# LED_BUFFER.net
KiCad netlist of a schematic drawn in Altium Designer
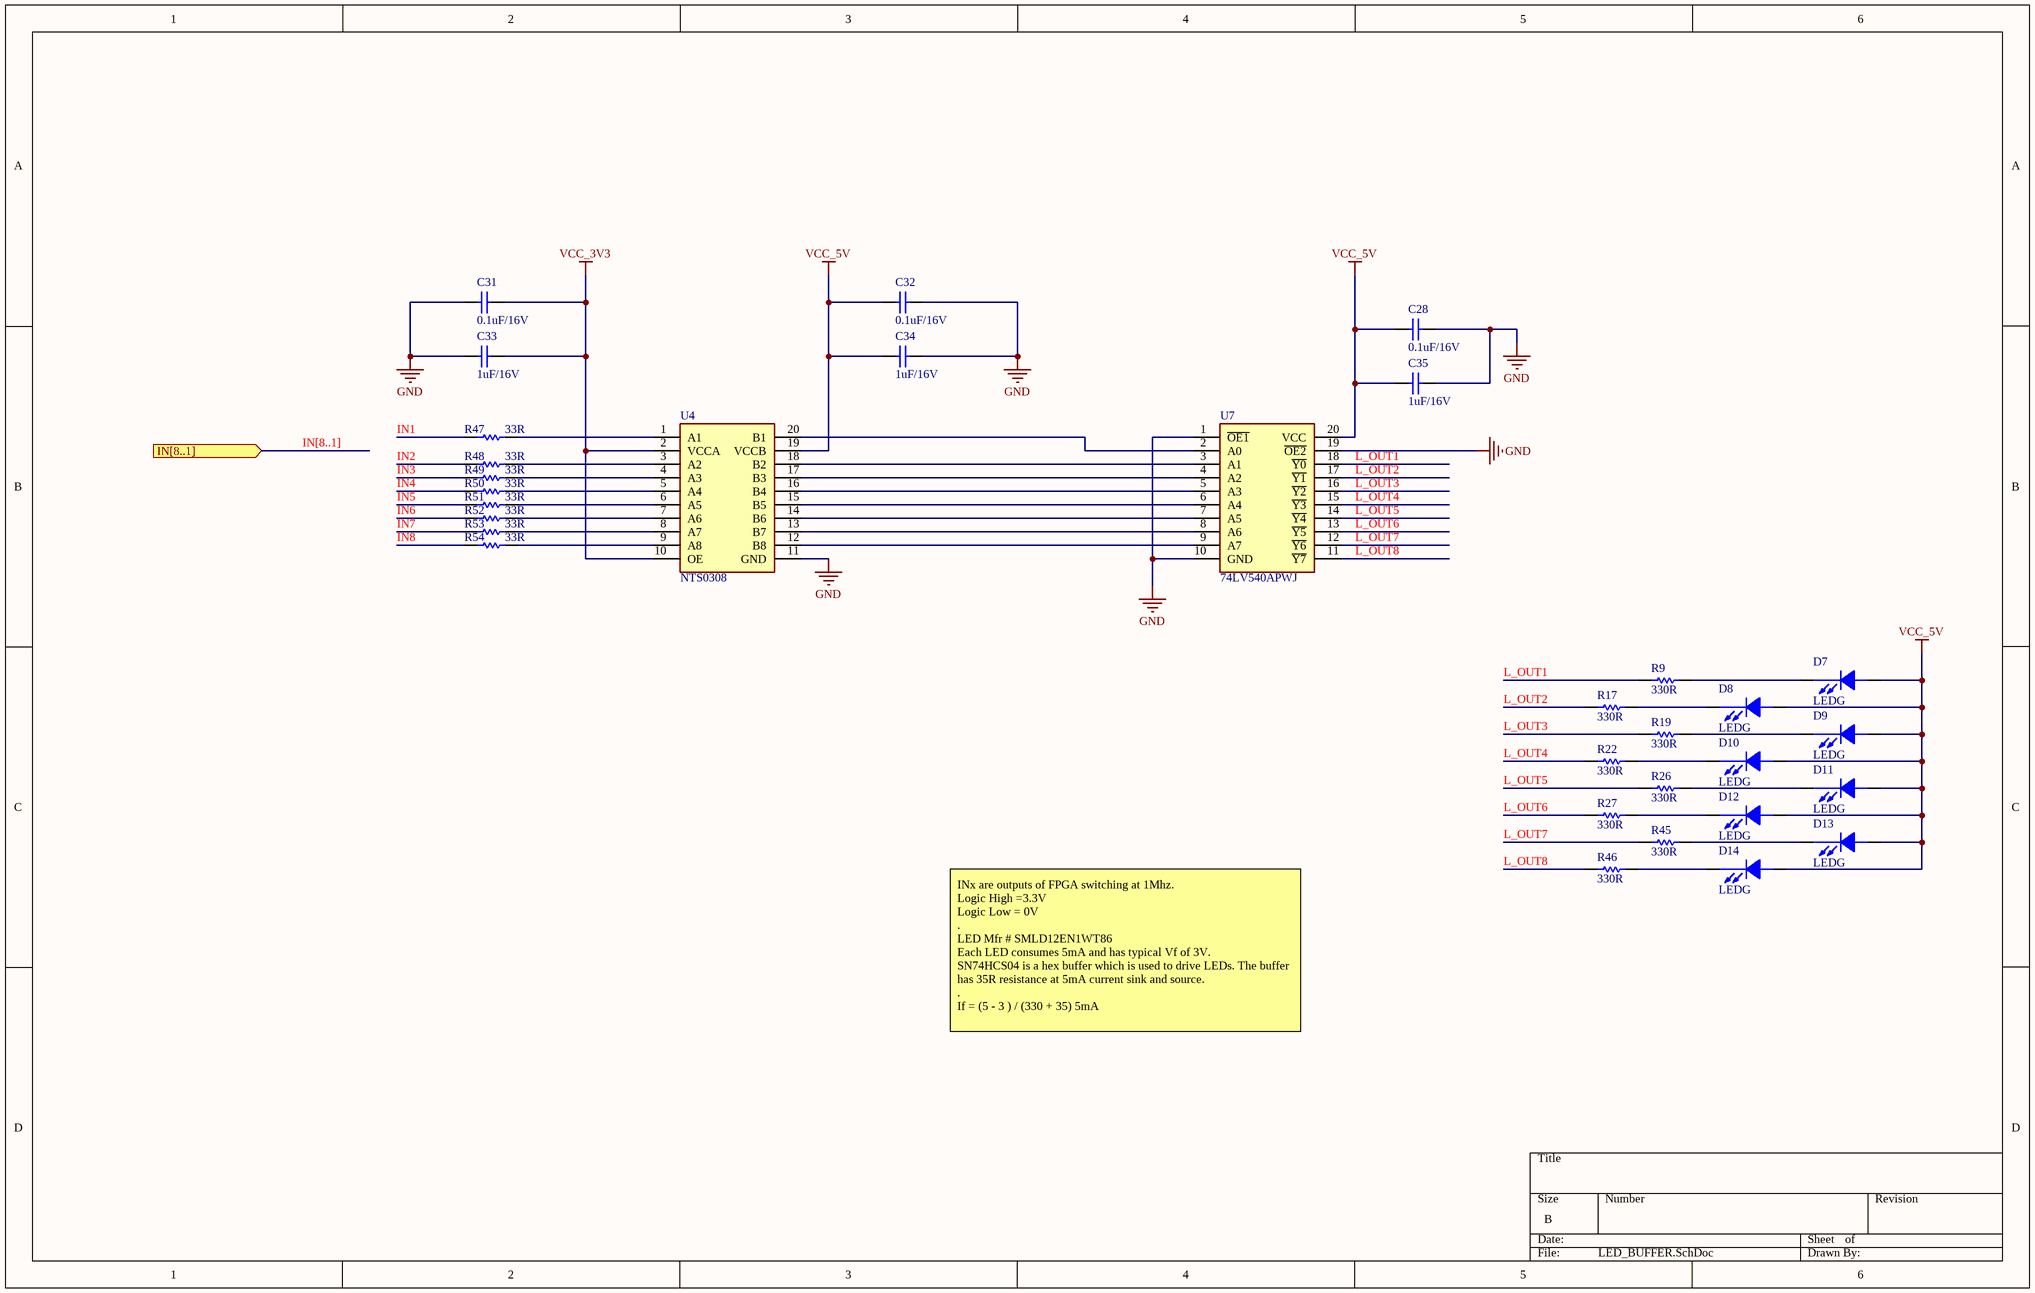
[diagram p0: LED_BUFFER.SchDoc]

(export (version "E")
  (design (tool "Eeschema 10.0.6"))
  (components
    (comp (ref "C28")
      (value "0.1uF/16V")
      (footprint "0603C")
      (description "Multilayer Ceramic Capacitors MLCC - SMD/SMT 0603 16VDC 0.1uF 10% X7R AEC-Q200")
      (fields (field (name "MFR") "Taiyo Yuden") (field (name "MFR PART NO") "EMK107B7104KAHT"))
      (libsource (lib "Miscellaneous Devices") (part "Cap"))
    )
    (comp (ref "C31")
      (value "0.1uF/16V")
      (footprint "0603C")
      (description "Multilayer Ceramic Capacitors MLCC - SMD/SMT 0603 16VDC 0.1uF 10% X7R AEC-Q200")
      (fields (field (name "MFR") "Taiyo Yuden") (field (name "MFR PART NO") "EMK107B7104KAHT"))
      (libsource (lib "Miscellaneous Devices") (part "Cap"))
    )
    (comp (ref "C32")
      (value "0.1uF/16V")
      (footprint "0603C")
      (description "Multilayer Ceramic Capacitors MLCC - SMD/SMT 0603 16VDC 0.1uF 10% X7R AEC-Q200")
      (fields (field (name "MFR") "Taiyo Yuden") (field (name "MFR PART NO") "EMK107B7104KAHT"))
      (libsource (lib "Miscellaneous Devices") (part "Cap"))
    )
    (comp (ref "C33")
      (value "1uF/16V")
      (footprint "0603C")
      (description "Multilayer Ceramic Capacitors MLCC - SMD/SMT 16volts 1uF X7R 10%")
      (fields (field (name "MFR") "KEMET") (field (name "MFR PART NO") "C0603C105K4RACTU"))
      (libsource (lib "Miscellaneous Devices") (part "Cap"))
    )
    (comp (ref "C34")
      (value "1uF/16V")
      (footprint "0603C")
      (description "Multilayer Ceramic Capacitors MLCC - SMD/SMT 16volts 1uF X7R 10%")
      (fields (field (name "MFR") "KEMET") (field (name "MFR PART NO") "C0603C105K4RACTU"))
      (libsource (lib "Miscellaneous Devices") (part "Cap"))
    )
    (comp (ref "C35")
      (value "1uF/16V")
      (footprint "0603C")
      (description "Multilayer Ceramic Capacitors MLCC - SMD/SMT 16volts 1uF X7R 10%")
      (fields (field (name "MFR") "KEMET") (field (name "MFR PART NO") "C0603C105K4RACTU"))
      (libsource (lib "Miscellaneous Devices") (part "Cap"))
    )
    (comp (ref "D7")
      (value "LEDG")
      (footprint "LED_0603")
      (description "Standard LEDs - SMD Grn 527nm; 140mcd 0603; 70mW")
      (fields (field (name "MFR") "ROHM Semiconductor") (field (name "MFR PART NO") "SMLD12EN1WT86"))
      (libsource (lib "de20") (part "LED"))
    )
    (comp (ref "D8")
      (value "LEDG")
      (footprint "LED_0603")
      (description "Standard LEDs - SMD Grn 527nm; 140mcd 0603; 70mW")
      (fields (field (name "MFR") "ROHM Semiconductor") (field (name "MFR PART NO") "SMLD12EN1WT86"))
      (libsource (lib "de20") (part "LED"))
    )
    (comp (ref "D9")
      (value "LEDG")
      (footprint "LED_0603")
      (description "Standard LEDs - SMD Grn 527nm; 140mcd 0603; 70mW")
      (fields (field (name "MFR") "ROHM Semiconductor") (field (name "MFR PART NO") "SMLD12EN1WT86"))
      (libsource (lib "de20") (part "LED"))
    )
    (comp (ref "D10")
      (value "LEDG")
      (footprint "LED_0603")
      (description "Standard LEDs - SMD Grn 527nm; 140mcd 0603; 70mW")
      (fields (field (name "MFR") "ROHM Semiconductor") (field (name "MFR PART NO") "SMLD12EN1WT86"))
      (libsource (lib "de20") (part "LED"))
    )
    (comp (ref "D11")
      (value "LEDG")
      (footprint "LED_0603")
      (description "Standard LEDs - SMD Grn 527nm; 140mcd 0603; 70mW")
      (fields (field (name "MFR") "ROHM Semiconductor") (field (name "MFR PART NO") "SMLD12EN1WT86"))
      (libsource (lib "de20") (part "LED"))
    )
    (comp (ref "D12")
      (value "LEDG")
      (footprint "LED_0603")
      (description "Standard LEDs - SMD Grn 527nm; 140mcd 0603; 70mW")
      (fields (field (name "MFR") "ROHM Semiconductor") (field (name "MFR PART NO") "SMLD12EN1WT86"))
      (libsource (lib "de20") (part "LED"))
    )
    (comp (ref "D13")
      (value "LEDG")
      (footprint "LED_0603")
      (description "Standard LEDs - SMD Grn 527nm; 140mcd 0603; 70mW")
      (fields (field (name "MFR") "ROHM Semiconductor") (field (name "MFR PART NO") "SMLD12EN1WT86"))
      (libsource (lib "de20") (part "LED"))
    )
    (comp (ref "D14")
      (value "LEDG")
      (footprint "LED_0603")
      (description "Standard LEDs - SMD Grn 527nm; 140mcd 0603; 70mW")
      (fields (field (name "MFR") "ROHM Semiconductor") (field (name "MFR PART NO") "SMLD12EN1WT86"))
      (libsource (lib "de20") (part "LED"))
    )
    (comp (ref "R9")
      (value "330R")
      (footprint "0603R")
      (description "Thick Film Resistors - SMD 1/10Watt 330ohms 1% Commercial Use")
      (fields (field (name "MFR") "Vishay / Dale") (field (name "MFR PART NO") "CRCW0603330RFKEAC"))
      (libsource (lib "Miscellaneous Devices") (part "Res1"))
    )
    (comp (ref "R17")
      (value "330R")
      (footprint "0603R")
      (description "Thick Film Resistors - SMD 1/10Watt 330ohms 1% Commercial Use")
      (fields (field (name "MFR") "Vishay / Dale") (field (name "MFR PART NO") "CRCW0603330RFKEAC"))
      (libsource (lib "Miscellaneous Devices") (part "Res1"))
    )
    (comp (ref "R19")
      (value "330R")
      (footprint "0603R")
      (description "Thick Film Resistors - SMD 1/10Watt 330ohms 1% Commercial Use")
      (fields (field (name "MFR") "Vishay / Dale") (field (name "MFR PART NO") "CRCW0603330RFKEAC"))
      (libsource (lib "Miscellaneous Devices") (part "Res1"))
    )
    (comp (ref "R22")
      (value "330R")
      (footprint "0603R")
      (description "Thick Film Resistors - SMD 1/10Watt 330ohms 1% Commercial Use")
      (fields (field (name "MFR") "Vishay / Dale") (field (name "MFR PART NO") "CRCW0603330RFKEAC"))
      (libsource (lib "Miscellaneous Devices") (part "Res1"))
    )
    (comp (ref "R26")
      (value "330R")
      (footprint "0603R")
      (description "Thick Film Resistors - SMD 1/10Watt 330ohms 1% Commercial Use")
      (fields (field (name "MFR") "Vishay / Dale") (field (name "MFR PART NO") "CRCW0603330RFKEAC"))
      (libsource (lib "Miscellaneous Devices") (part "Res1"))
    )
    (comp (ref "R27")
      (value "330R")
      (footprint "0603R")
      (description "Thick Film Resistors - SMD 1/10Watt 330ohms 1% Commercial Use")
      (fields (field (name "MFR") "Vishay / Dale") (field (name "MFR PART NO") "CRCW0603330RFKEAC"))
      (libsource (lib "Miscellaneous Devices") (part "Res1"))
    )
    (comp (ref "R45")
      (value "330R")
      (footprint "0603R")
      (description "Thick Film Resistors - SMD 1/10Watt 330ohms 1% Commercial Use")
      (fields (field (name "MFR") "Vishay / Dale") (field (name "MFR PART NO") "CRCW0603330RFKEAC"))
      (libsource (lib "Miscellaneous Devices") (part "Res1"))
    )
    (comp (ref "R46")
      (value "330R")
      (footprint "0603R")
      (description "Thick Film Resistors - SMD 1/10Watt 330ohms 1% Commercial Use")
      (fields (field (name "MFR") "Vishay / Dale") (field (name "MFR PART NO") "CRCW0603330RFKEAC"))
      (libsource (lib "Miscellaneous Devices") (part "Res1"))
    )
    (comp (ref "R47")
      (value "33R")
      (footprint "0603R")
      (description "Thick Film Resistors - SMD 1/10Watt 33ohms 1% Commercial Use")
      (fields (field (name "MFR") "Vishay / Dale") (field (name "MFR PART NO") "CRCW060333R0FKEAC"))
      (libsource (lib "Miscellaneous Devices") (part "Res1"))
    )
    (comp (ref "R48")
      (value "33R")
      (footprint "0603R")
      (description "Thick Film Resistors - SMD 1/10Watt 33ohms 1% Commercial Use")
      (fields (field (name "MFR") "Vishay / Dale") (field (name "MFR PART NO") "CRCW060333R0FKEAC"))
      (libsource (lib "Miscellaneous Devices") (part "Res1"))
    )
    (comp (ref "R49")
      (value "33R")
      (footprint "0603R")
      (description "Thick Film Resistors - SMD 1/10Watt 33ohms 1% Commercial Use")
      (fields (field (name "MFR") "Vishay / Dale") (field (name "MFR PART NO") "CRCW060333R0FKEAC"))
      (libsource (lib "Miscellaneous Devices") (part "Res1"))
    )
    (comp (ref "R50")
      (value "33R")
      (footprint "0603R")
      (description "Thick Film Resistors - SMD 1/10Watt 33ohms 1% Commercial Use")
      (fields (field (name "MFR") "Vishay / Dale") (field (name "MFR PART NO") "CRCW060333R0FKEAC"))
      (libsource (lib "Miscellaneous Devices") (part "Res1"))
    )
    (comp (ref "R51")
      (value "33R")
      (footprint "0603R")
      (description "Thick Film Resistors - SMD 1/10Watt 33ohms 1% Commercial Use")
      (fields (field (name "MFR") "Vishay / Dale") (field (name "MFR PART NO") "CRCW060333R0FKEAC"))
      (libsource (lib "Miscellaneous Devices") (part "Res1"))
    )
    (comp (ref "R52")
      (value "33R")
      (footprint "0603R")
      (description "Thick Film Resistors - SMD 1/10Watt 33ohms 1% Commercial Use")
      (fields (field (name "MFR") "Vishay / Dale") (field (name "MFR PART NO") "CRCW060333R0FKEAC"))
      (libsource (lib "Miscellaneous Devices") (part "Res1"))
    )
    (comp (ref "R53")
      (value "33R")
      (footprint "0603R")
      (description "Thick Film Resistors - SMD 1/10Watt 33ohms 1% Commercial Use")
      (fields (field (name "MFR") "Vishay / Dale") (field (name "MFR PART NO") "CRCW060333R0FKEAC"))
      (libsource (lib "Miscellaneous Devices") (part "Res1"))
    )
    (comp (ref "R54")
      (value "33R")
      (footprint "0603R")
      (description "Thick Film Resistors - SMD 1/10Watt 33ohms 1% Commercial Use")
      (fields (field (name "MFR") "Vishay / Dale") (field (name "MFR PART NO") "CRCW060333R0FKEAC"))
      (libsource (lib "Miscellaneous Devices") (part "Res1"))
    )
    (comp (ref "U4")
      (value "NTS0308")
      (footprint "NTS0308EPWJ")
      (fields
        (field (name "MFR") "NXP Semiconductors")
        (field (name "MFR PART NO") "NTS0308EPWJ")
        (field (name "STOCKIEST PART NO") "771-NTS0308EPWJ")
      )
      (libsource (lib "*") (part "TXS0108EPWR"))
    )
    (comp (ref "U7")
      (value "74LV540APWJ")
      (footprint "SamacSys:SOP65P640X110-20N")
      (description "Buffers & Line Drivers BUFFER LINE DRIVER")
      (fields (field (name "MFR") "Nexperia") (field (name "STOCKIEST PART NO") "771-74LV540APWJ"))
      (libsource (lib "*") (part "74LV540APWJ"))
    )
  )
  (nets
    (net (code "1") (name "/IN1") (class "Default")
      (node (ref "R47") (pin "2") (pinfunction "2_2") (pintype "passive"))
    )
    (net (code "2") (name "/IN2") (class "Default")
      (node (ref "R48") (pin "2") (pinfunction "2_2") (pintype "passive"))
    )
    (net (code "3") (name "/IN3") (class "Default")
      (node (ref "R49") (pin "2") (pinfunction "2_2") (pintype "passive"))
    )
    (net (code "4") (name "/IN4") (class "Default")
      (node (ref "R50") (pin "2") (pinfunction "2_2") (pintype "passive"))
    )
    (net (code "5") (name "/IN5") (class "Default")
      (node (ref "R51") (pin "2") (pinfunction "2_2") (pintype "passive"))
    )
    (net (code "6") (name "/IN6") (class "Default")
      (node (ref "R52") (pin "2") (pinfunction "2_2") (pintype "passive"))
    )
    (net (code "7") (name "/IN7") (class "Default")
      (node (ref "R53") (pin "2") (pinfunction "2_2") (pintype "passive"))
    )
    (net (code "8") (name "/IN8") (class "Default")
      (node (ref "R54") (pin "2") (pinfunction "2_2") (pintype "passive"))
    )
    (net (code "10") (name "/L_OUT1") (class "Default")
      (node (ref "R9") (pin "2") (pinfunction "2_2") (pintype "passive"))
      (node (ref "U7") (pin "18") (pinfunction "~{Y0}_18") (pintype "passive"))
    )
    (net (code "11") (name "/L_OUT2") (class "Default")
      (node (ref "R17") (pin "2") (pinfunction "2_2") (pintype "passive"))
      (node (ref "U7") (pin "17") (pinfunction "~{Y1}_17") (pintype "passive"))
    )
    (net (code "12") (name "/L_OUT3") (class "Default")
      (node (ref "R19") (pin "2") (pinfunction "2_2") (pintype "passive"))
      (node (ref "U7") (pin "16") (pinfunction "~{Y2}_16") (pintype "passive"))
    )
    (net (code "13") (name "/L_OUT4") (class "Default")
      (node (ref "R22") (pin "2") (pinfunction "2_2") (pintype "passive"))
      (node (ref "U7") (pin "15") (pinfunction "~{Y3}_15") (pintype "passive"))
    )
    (net (code "14") (name "/L_OUT5") (class "Default")
      (node (ref "R26") (pin "2") (pinfunction "2_2") (pintype "passive"))
      (node (ref "U7") (pin "14") (pinfunction "~{Y4}_14") (pintype "passive"))
    )
    (net (code "15") (name "/L_OUT6") (class "Default")
      (node (ref "R27") (pin "2") (pinfunction "2_2") (pintype "passive"))
      (node (ref "U7") (pin "13") (pinfunction "~{Y5}_13") (pintype "passive"))
    )
    (net (code "16") (name "/L_OUT7") (class "Default")
      (node (ref "R45") (pin "2") (pinfunction "2_2") (pintype "passive"))
      (node (ref "U7") (pin "12") (pinfunction "~{Y6}_12") (pintype "passive"))
    )
    (net (code "17") (name "/L_OUT8") (class "Default")
      (node (ref "R46") (pin "2") (pinfunction "2_2") (pintype "passive"))
      (node (ref "U7") (pin "11") (pinfunction "~{Y7}_11") (pintype "passive"))
    )
    (net (code "18") (name "GND") (class "Default")
      (node (ref "C28") (pin "2") (pinfunction "2_2") (pintype "passive"))
      (node (ref "C31") (pin "1") (pinfunction "1_1") (pintype "passive"))
      (node (ref "C32") (pin "2") (pinfunction "2_2") (pintype "passive"))
      (node (ref "C33") (pin "1") (pinfunction "1_1") (pintype "passive"))
      (node (ref "C34") (pin "2") (pinfunction "2_2") (pintype "passive"))
      (node (ref "C35") (pin "2") (pinfunction "2_2") (pintype "passive"))
      (node (ref "U4") (pin "11") (pinfunction "GND_11") (pintype "passive"))
      (node (ref "U7") (pin "1") (pinfunction "~{OE1}_1") (pintype "passive"))
      (node (ref "U7") (pin "10") (pinfunction "GND_10") (pintype "passive"))
      (node (ref "U7") (pin "19") (pinfunction "~{OE2}_19") (pintype "passive"))
    )
    (net (code "19") (name "Net-(D7-CATHODE)") (class "Default")
      (node (ref "D7") (pin "2") (pinfunction "CATHODE_2") (pintype "passive"))
      (node (ref "R9") (pin "1") (pinfunction "1_1") (pintype "passive"))
    )
    (net (code "20") (name "Net-(D8-CATHODE)") (class "Default")
      (node (ref "D8") (pin "2") (pinfunction "CATHODE_2") (pintype "passive"))
      (node (ref "R17") (pin "1") (pinfunction "1_1") (pintype "passive"))
    )
    (net (code "21") (name "Net-(D9-CATHODE)") (class "Default")
      (node (ref "D9") (pin "2") (pinfunction "CATHODE_2") (pintype "passive"))
      (node (ref "R19") (pin "1") (pinfunction "1_1") (pintype "passive"))
    )
    (net (code "22") (name "Net-(D10-CATHODE)") (class "Default")
      (node (ref "D10") (pin "2") (pinfunction "CATHODE_2") (pintype "passive"))
      (node (ref "R22") (pin "1") (pinfunction "1_1") (pintype "passive"))
    )
    (net (code "23") (name "Net-(D11-CATHODE)") (class "Default")
      (node (ref "D11") (pin "2") (pinfunction "CATHODE_2") (pintype "passive"))
      (node (ref "R26") (pin "1") (pinfunction "1_1") (pintype "passive"))
    )
    (net (code "24") (name "Net-(D12-CATHODE)") (class "Default")
      (node (ref "D12") (pin "2") (pinfunction "CATHODE_2") (pintype "passive"))
      (node (ref "R27") (pin "1") (pinfunction "1_1") (pintype "passive"))
    )
    (net (code "25") (name "Net-(D13-CATHODE)") (class "Default")
      (node (ref "D13") (pin "2") (pinfunction "CATHODE_2") (pintype "passive"))
      (node (ref "R45") (pin "1") (pinfunction "1_1") (pintype "passive"))
    )
    (net (code "26") (name "Net-(D14-CATHODE)") (class "Default")
      (node (ref "D14") (pin "2") (pinfunction "CATHODE_2") (pintype "passive"))
      (node (ref "R46") (pin "1") (pinfunction "1_1") (pintype "passive"))
    )
    (net (code "27") (name "Net-(U4-A1)") (class "Default")
      (node (ref "R47") (pin "1") (pinfunction "1_1") (pintype "passive"))
      (node (ref "U4") (pin "1") (pinfunction "A1_1") (pintype "passive"))
    )
    (net (code "28") (name "Net-(U4-A2)") (class "Default")
      (node (ref "R48") (pin "1") (pinfunction "1_1") (pintype "passive"))
      (node (ref "U4") (pin "3") (pinfunction "A2_3") (pintype "passive"))
    )
    (net (code "29") (name "Net-(U4-A3)") (class "Default")
      (node (ref "R49") (pin "1") (pinfunction "1_1") (pintype "passive"))
      (node (ref "U4") (pin "4") (pinfunction "A3_4") (pintype "passive"))
    )
    (net (code "30") (name "Net-(U4-A4)") (class "Default")
      (node (ref "R50") (pin "1") (pinfunction "1_1") (pintype "passive"))
      (node (ref "U4") (pin "5") (pinfunction "A4_5") (pintype "passive"))
    )
    (net (code "31") (name "Net-(U4-A5)") (class "Default")
      (node (ref "R51") (pin "1") (pinfunction "1_1") (pintype "passive"))
      (node (ref "U4") (pin "6") (pinfunction "A5_6") (pintype "passive"))
    )
    (net (code "32") (name "Net-(U4-A6)") (class "Default")
      (node (ref "R52") (pin "1") (pinfunction "1_1") (pintype "passive"))
      (node (ref "U4") (pin "7") (pinfunction "A6_7") (pintype "passive"))
    )
    (net (code "33") (name "Net-(U4-A7)") (class "Default")
      (node (ref "R53") (pin "1") (pinfunction "1_1") (pintype "passive"))
      (node (ref "U4") (pin "8") (pinfunction "A7_8") (pintype "passive"))
    )
    (net (code "34") (name "Net-(U4-A8)") (class "Default")
      (node (ref "R54") (pin "1") (pinfunction "1_1") (pintype "passive"))
      (node (ref "U4") (pin "9") (pinfunction "A8_9") (pintype "passive"))
    )
    (net (code "35") (name "Net-(U4-B1)") (class "Default")
      (node (ref "U4") (pin "20") (pinfunction "B1_20") (pintype "passive"))
      (node (ref "U7") (pin "2") (pinfunction "A0_2") (pintype "passive"))
    )
    (net (code "36") (name "Net-(U4-B2)") (class "Default")
      (node (ref "U4") (pin "18") (pinfunction "B2_18") (pintype "passive"))
      (node (ref "U7") (pin "3") (pinfunction "A1_3") (pintype "passive"))
    )
    (net (code "37") (name "Net-(U4-B3)") (class "Default")
      (node (ref "U4") (pin "17") (pinfunction "B3_17") (pintype "passive"))
      (node (ref "U7") (pin "4") (pinfunction "A2_4") (pintype "passive"))
    )
    (net (code "38") (name "Net-(U4-B4)") (class "Default")
      (node (ref "U4") (pin "16") (pinfunction "B4_16") (pintype "passive"))
      (node (ref "U7") (pin "5") (pinfunction "A3_5") (pintype "passive"))
    )
    (net (code "39") (name "Net-(U4-B5)") (class "Default")
      (node (ref "U4") (pin "15") (pinfunction "B5_15") (pintype "passive"))
      (node (ref "U7") (pin "6") (pinfunction "A4_6") (pintype "passive"))
    )
    (net (code "40") (name "Net-(U4-B6)") (class "Default")
      (node (ref "U4") (pin "14") (pinfunction "B6_14") (pintype "passive"))
      (node (ref "U7") (pin "7") (pinfunction "A5_7") (pintype "passive"))
    )
    (net (code "41") (name "Net-(U4-B7)") (class "Default")
      (node (ref "U4") (pin "13") (pinfunction "B7_13") (pintype "passive"))
      (node (ref "U7") (pin "8") (pinfunction "A6_8") (pintype "passive"))
    )
    (net (code "42") (name "Net-(U4-B8)") (class "Default")
      (node (ref "U4") (pin "12") (pinfunction "B8_12") (pintype "passive"))
      (node (ref "U7") (pin "9") (pinfunction "A7_9") (pintype "passive"))
    )
    (net (code "43") (name "VCC_3V3") (class "Default")
      (node (ref "C31") (pin "2") (pinfunction "2_2") (pintype "passive"))
      (node (ref "C33") (pin "2") (pinfunction "2_2") (pintype "passive"))
      (node (ref "U4") (pin "10") (pinfunction "OE_10") (pintype "passive"))
      (node (ref "U4") (pin "2") (pinfunction "VCCA_2") (pintype "passive"))
    )
    (net (code "44") (name "VCC_5V") (class "Default")
      (node (ref "C28") (pin "1") (pinfunction "1_1") (pintype "passive"))
      (node (ref "C32") (pin "1") (pinfunction "1_1") (pintype "passive"))
      (node (ref "C34") (pin "1") (pinfunction "1_1") (pintype "passive"))
      (node (ref "C35") (pin "1") (pinfunction "1_1") (pintype "passive"))
      (node (ref "D10") (pin "1") (pinfunction "ANODE_1") (pintype "passive"))
      (node (ref "D11") (pin "1") (pinfunction "ANODE_1") (pintype "passive"))
      (node (ref "D12") (pin "1") (pinfunction "ANODE_1") (pintype "passive"))
      (node (ref "D13") (pin "1") (pinfunction "ANODE_1") (pintype "passive"))
      (node (ref "D14") (pin "1") (pinfunction "ANODE_1") (pintype "passive"))
      (node (ref "D7") (pin "1") (pinfunction "ANODE_1") (pintype "passive"))
      (node (ref "D8") (pin "1") (pinfunction "ANODE_1") (pintype "passive"))
      (node (ref "D9") (pin "1") (pinfunction "ANODE_1") (pintype "passive"))
      (node (ref "U4") (pin "19") (pinfunction "VCCB_19") (pintype "passive"))
      (node (ref "U7") (pin "20") (pinfunction "VCC_20") (pintype "passive"))
    )
  )
)
